# DXP_1602.net
KiCad netlist of a schematic drawn in Altium Designer
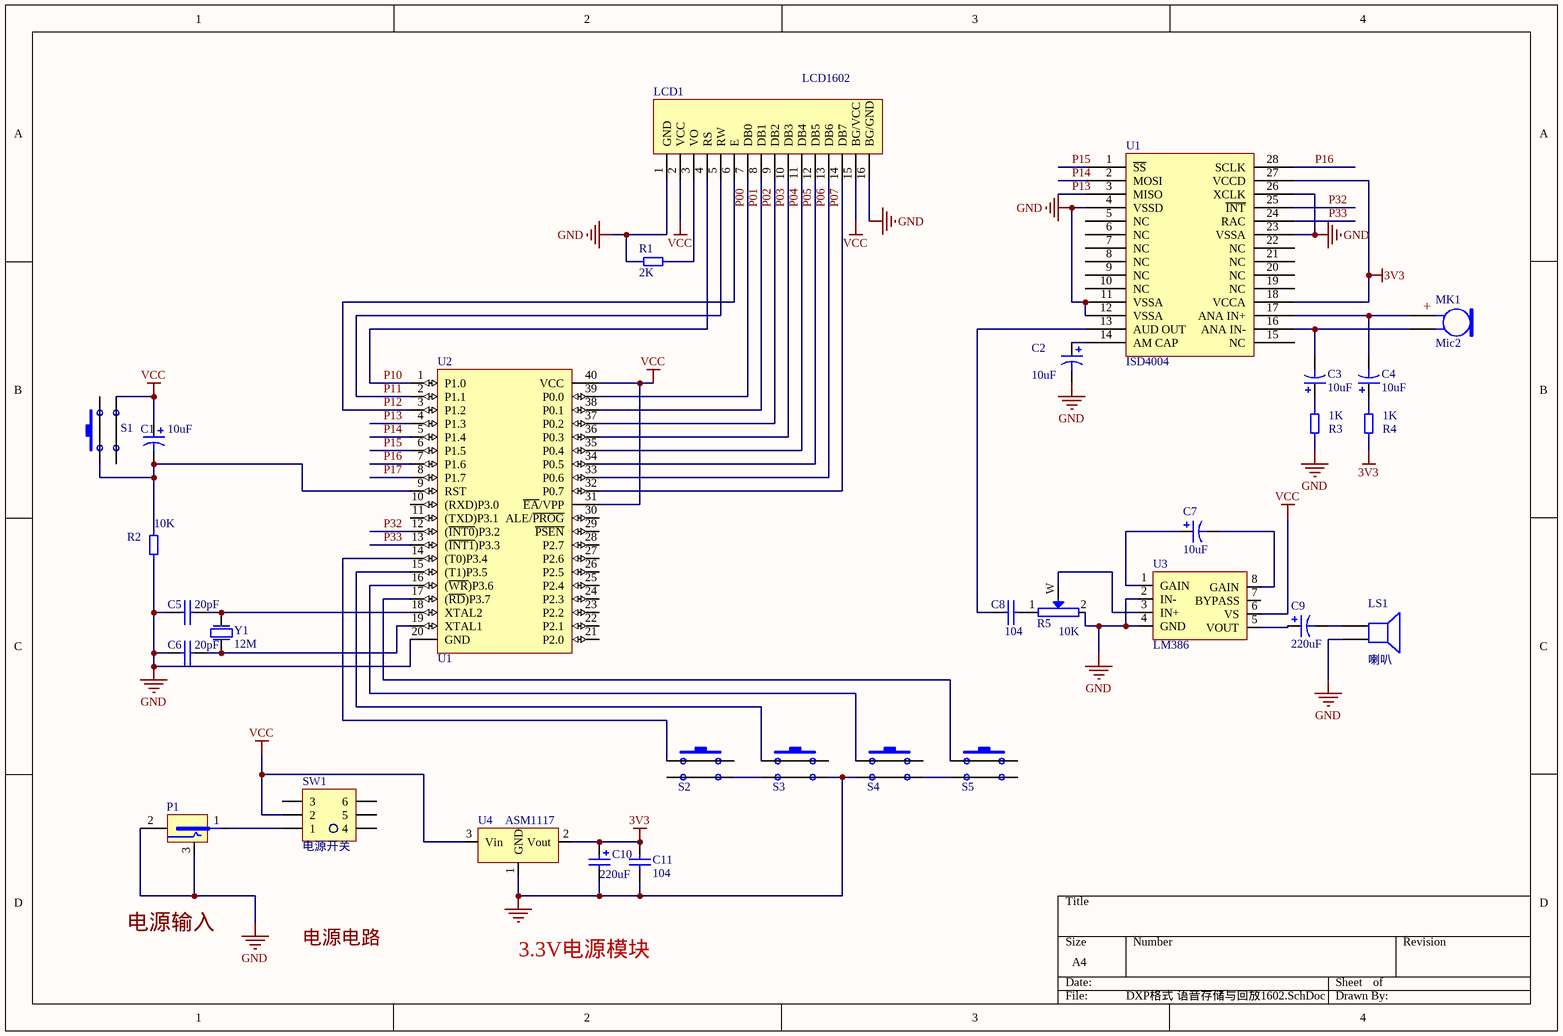
[diagram p0: DXP格式 语音存储与回放1602.SchDoc]

(export (version "E")
  (design (tool "Eeschema 10.0.6"))
  (components
    (comp (ref "C1")
      (value "10uF")
      (footprint "C_10")
      (description "Polarized Capacitor (Radial)")
      (fields (field (name "PUBLISHER") "Altium Limited"))
      (libsource (lib "简易动环监控系统") (part "Cap Pol1"))
    )
    (comp (ref "C2")
      (value "10uF")
      (footprint "C_10")
      (description "Polarized Capacitor (Radial)")
      (fields (field (name "PUBLISHER") "Altium Limited"))
      (libsource (lib "简易动环监控系统") (part "Cap Pol1"))
    )
    (comp (ref "C3")
      (value "10uF")
      (footprint "C_10")
      (description "Polarized Capacitor (Radial)")
      (fields (field (name "PUBLISHER") "Altium Limited"))
      (libsource (lib "简易动环监控系统") (part "Cap Pol1"))
    )
    (comp (ref "C4")
      (value "10uF")
      (footprint "C_10")
      (description "Polarized Capacitor (Radial)")
      (fields (field (name "PUBLISHER") "Altium Limited"))
      (libsource (lib "简易动环监控系统") (part "Cap Pol1"))
    )
    (comp (ref "C5")
      (value "20pF")
      (footprint "CAP CP")
      (description "电容")
      (libsource (lib "C8051F020最小2") (part "CAP"))
    )
    (comp (ref "C6")
      (value "20pF")
      (footprint "CAP CP")
      (description "电容")
      (libsource (lib "C8051F020最小2") (part "CAP"))
    )
    (comp (ref "C7")
      (value "10uF")
      (footprint "CAP_470")
      (description "Polarized Capacitor (Radial)")
      (fields (field (name "PUBLISHER") "Altium Limited"))
      (libsource (lib "简易动环监控系统") (part "Cap Pol1"))
    )
    (comp (ref "C8")
      (value "104")
      (footprint "CAP5")
      (description "电容")
      (libsource (lib "C8051F020最小2") (part "CAP"))
    )
    (comp (ref "C9")
      (value "220uF")
      (footprint "CAP_470")
      (description "Polarized Capacitor (Radial)")
      (fields (field (name "PUBLISHER") "Altium Limited"))
      (libsource (lib "简易动环监控系统") (part "Cap Pol1"))
    )
    (comp (ref "C10")
      (value "220uF")
      (footprint "C_10")
      (description "220uF 470uF 外径8mm 引脚3mm")
      (fields (field (name "Comment") "220uf"))
      (libsource (lib "*") (part "CAP 470uF"))
    )
    (comp (ref "C11")
      (value "104")
      (footprint "CAP CP")
      (description "瓷片电容")
      (libsource (lib "*") (part "CAP"))
    )
    (comp (ref "LCD1") (value "LCD1602") (footprint "1602") (libsource (lib "实用原理图库") (part "LCD1602")))
    (comp (ref "LS1")
      (value "喇叭")
      (footprint "SIP2")
      (description "Loudspeaker")
      (fields (field (name "PUBLISHER") "Altium Limited"))
      (libsource (lib "Miscellaneous Devices") (part "Speaker"))
    )
    (comp (ref "MK1")
      (value "Mic2")
      (footprint "mic")
      (description "Microphone")
      (fields (field (name "PUBLISHER") "Altium Limited"))
      (libsource (lib "Miscellaneous Devices") (part "Mic2"))
    )
    (comp (ref "P1") (value "电源输入") (footprint "DC2.1") (libsource (lib "我自己的") (part "POWER")))
    (comp (ref "R1") (value "2K") (footprint "AXIAL0.3") (libsource (lib "C8051F020最小2") (part "RES2")))
    (comp (ref "R2") (value "10K") (footprint "AXIAL0.3") (libsource (lib "C8051F020最小2") (part "RES2")))
    (comp (ref "R3") (value "1K") (footprint "AXIAL0.3") (libsource (lib "C8051F020最小2") (part "RES2")))
    (comp (ref "R4") (value "1K") (footprint "AXIAL0.3") (libsource (lib "C8051F020最小2") (part "RES2")))
    (comp (ref "R5")
      (value "10K")
      (footprint "RES")
      (description "可调电位器")
      (fields (field (name "Comment") "RES  KB"))
      (libsource (lib "JIANYANG") (part "RES  KB"))
    )
    (comp (ref "S1") (value "SW") (footprint "key") (libsource (lib "我自己的") (part "SW1_key")))
    (comp (ref "S2") (value "SW") (footprint "key") (libsource (lib "我自己的") (part "SW1_key")))
    (comp (ref "S3") (value "SW") (footprint "key") (libsource (lib "我自己的") (part "SW1_key")))
    (comp (ref "S4") (value "SW") (footprint "key") (libsource (lib "我自己的") (part "SW1_key")))
    (comp (ref "S5") (value "SW") (footprint "key") (libsource (lib "我自己的") (part "SW1_key")))
    (comp (ref "SW1") (value "电源开关") (footprint "sw_自锁 1") (libsource (lib "我自己的") (part "SW1")))
    (comp (ref "U1") (value "ISD4004") (footprint "DIP28") (libsource (lib "*") (part "ISD4004")))
    (comp (ref "U2") (value "U1") (footprint "DIP40 - 做板") (libsource (lib "实验板原理图") (part "U1")))
    (comp (ref "U3") (value "LM386") (footprint "DIP8") (libsource (lib "我自己的") (part "LM386")))
    (comp (ref "U4") (value "ASM1117") (footprint "ASM1117") (libsource (lib "*") (part "ASM1117")))
    (comp (ref "Y1")
      (value "12M")
      (footprint "XTAL")
      (description "Crystal Oscillator")
      (libsource (lib "C8051F020最小2") (part "16M"))
    )
  )
  (nets
    (net (code "2") (name "/P00") (class "Default")
      (node (ref "LCD1") (pin "7") (pinfunction "DB0_7") (pintype "passive"))
      (node (ref "U2") (pin "39") (pinfunction "P0.0_39") (pintype "bidirectional"))
    )
    (net (code "3") (name "/P01") (class "Default")
      (node (ref "LCD1") (pin "8") (pinfunction "DB1_8") (pintype "passive"))
      (node (ref "U2") (pin "38") (pinfunction "P0.1_38") (pintype "bidirectional"))
    )
    (net (code "4") (name "/P02") (class "Default")
      (node (ref "LCD1") (pin "9") (pinfunction "DB2_9") (pintype "passive"))
      (node (ref "U2") (pin "37") (pinfunction "P0.2_37") (pintype "bidirectional"))
    )
    (net (code "5") (name "/P03") (class "Default")
      (node (ref "LCD1") (pin "10") (pinfunction "DB3_10") (pintype "passive"))
      (node (ref "U2") (pin "36") (pinfunction "P0.3_36") (pintype "bidirectional"))
    )
    (net (code "6") (name "/P04") (class "Default")
      (node (ref "LCD1") (pin "11") (pinfunction "DB4_11") (pintype "passive"))
      (node (ref "U2") (pin "35") (pinfunction "P0.4_35") (pintype "bidirectional"))
    )
    (net (code "7") (name "/P05") (class "Default")
      (node (ref "LCD1") (pin "12") (pinfunction "DB5_12") (pintype "passive"))
      (node (ref "U2") (pin "34") (pinfunction "P0.5_34") (pintype "bidirectional"))
    )
    (net (code "8") (name "/P06") (class "Default")
      (node (ref "LCD1") (pin "13") (pinfunction "DB6_13") (pintype "passive"))
      (node (ref "U2") (pin "33") (pinfunction "P0.6_33") (pintype "bidirectional"))
    )
    (net (code "9") (name "/P07") (class "Default")
      (node (ref "LCD1") (pin "14") (pinfunction "DB7_14") (pintype "passive"))
      (node (ref "U2") (pin "32") (pinfunction "P0.7_32") (pintype "bidirectional"))
    )
    (net (code "10") (name "/P10") (class "Default")
      (node (ref "LCD1") (pin "4") (pinfunction "RS_4") (pintype "passive"))
      (node (ref "U2") (pin "1") (pinfunction "P1.0_1") (pintype "bidirectional"))
    )
    (net (code "11") (name "/P11") (class "Default")
      (node (ref "LCD1") (pin "5") (pinfunction "RW_5") (pintype "passive"))
      (node (ref "U2") (pin "2") (pinfunction "P1.1_2") (pintype "bidirectional"))
    )
    (net (code "12") (name "/P12") (class "Default")
      (node (ref "LCD1") (pin "6") (pinfunction "E_6") (pintype "passive"))
      (node (ref "U2") (pin "3") (pinfunction "P1.2_3") (pintype "bidirectional"))
    )
    (net (code "13") (name "/P13") (class "Default")
      (node (ref "U1") (pin "3") (pinfunction "MISO_3") (pintype "passive"))
      (node (ref "U2") (pin "4") (pinfunction "P1.3_4") (pintype "bidirectional"))
    )
    (net (code "14") (name "/P14") (class "Default")
      (node (ref "U1") (pin "2") (pinfunction "MOSI_2") (pintype "passive"))
      (node (ref "U2") (pin "5") (pinfunction "P1.4_5") (pintype "bidirectional"))
    )
    (net (code "15") (name "/P15") (class "Default")
      (node (ref "U1") (pin "1") (pinfunction "~{SS}_1") (pintype "passive"))
      (node (ref "U2") (pin "6") (pinfunction "P1.5_6") (pintype "bidirectional"))
    )
    (net (code "16") (name "/P16") (class "Default")
      (node (ref "U1") (pin "28") (pinfunction "SCLK_28") (pintype "passive"))
      (node (ref "U2") (pin "7") (pinfunction "P1.6_7") (pintype "bidirectional"))
    )
    (net (code "17") (name "/P17") (class "Default")
      (node (ref "U2") (pin "8") (pinfunction "P1.7_8") (pintype "bidirectional"))
    )
    (net (code "18") (name "/P32") (class "Default")
      (node (ref "U1") (pin "25") (pinfunction "~{INT}_25") (pintype "passive"))
      (node (ref "U2") (pin "12") (pinfunction "(~{INT0})P3.2_12") (pintype "bidirectional"))
    )
    (net (code "19") (name "/P33") (class "Default")
      (node (ref "U1") (pin "24") (pinfunction "RAC_24") (pintype "passive"))
      (node (ref "U2") (pin "13") (pinfunction "(~{INT1})P3.3_13") (pintype "bidirectional"))
    )
    (net (code "22") (name "3V3") (class "Default")
      (node (ref "C10") (pin "1") (pinfunction "1_1") (pintype "passive"))
      (node (ref "C11") (pin "2") (pinfunction "2_2") (pintype "passive"))
      (node (ref "R4") (pin "1") (pinfunction "1_1") (pintype "passive"))
      (node (ref "U1") (pin "18") (pinfunction "VCCA_18") (pintype "passive"))
      (node (ref "U1") (pin "27") (pinfunction "VCCD_27") (pintype "passive"))
      (node (ref "U4") (pin "2") (pinfunction "Vout_2") (pintype "passive"))
    )
    (net (code "23") (name "GND") (class "Default")
      (node (ref "C10") (pin "2") (pinfunction "2_2") (pintype "passive"))
      (node (ref "C11") (pin "1") (pinfunction "1_1") (pintype "passive"))
      (node (ref "C2") (pin "2") (pinfunction "2_2") (pintype "passive"))
      (node (ref "C5") (pin "1") (pinfunction "1_1") (pintype "passive"))
      (node (ref "C6") (pin "1") (pinfunction "1_1") (pintype "passive"))
      (node (ref "LCD1") (pin "1") (pinfunction "GND_1") (pintype "passive"))
      (node (ref "LCD1") (pin "16") (pinfunction "BG/GND_16") (pintype "passive"))
      (node (ref "LS1") (pin "2") (pinfunction "2_2") (pintype "passive"))
      (node (ref "P1") (pin "2") (pintype "passive"))
      (node (ref "P1") (pin "3") (pintype "passive"))
      (node (ref "R1") (pin "1") (pinfunction "1_1") (pintype "passive"))
      (node (ref "R2") (pin "1") (pinfunction "1_1") (pintype "passive"))
      (node (ref "R3") (pin "1") (pinfunction "1_1") (pintype "passive"))
      (node (ref "R5") (pin "2") (pintype "passive"))
      (node (ref "S3") (pin "2") (pinfunction "2_2") (pintype "passive"))
      (node (ref "S4") (pin "2") (pinfunction "2_2") (pintype "passive"))
      (node (ref "U1") (pin "11") (pinfunction "VSSA_11") (pintype "passive"))
      (node (ref "U1") (pin "12") (pinfunction "VSSA_12") (pintype "passive"))
      (node (ref "U1") (pin "23") (pinfunction "VSSA_23") (pintype "passive"))
      (node (ref "U1") (pin "26") (pinfunction "XCLK_26") (pintype "passive"))
      (node (ref "U1") (pin "4") (pinfunction "VSSD_4") (pintype "passive"))
      (node (ref "U2") (pin "20") (pinfunction "GND_20") (pintype "power_in"))
      (node (ref "U3") (pin "2") (pinfunction "IN-_2") (pintype "passive"))
      (node (ref "U3") (pin "4") (pinfunction "GND_4") (pintype "passive"))
      (node (ref "U4") (pin "1") (pinfunction "GND_1") (pintype "passive"))
    )
    (net (code "24") (name "Net-(C3-Pad1)") (class "Default")
      (node (ref "C3") (pin "1") (pinfunction "1_1") (pintype "passive"))
      (node (ref "R3") (pin "2") (pinfunction "2_2") (pintype "passive"))
    )
    (net (code "25") (name "Net-(C4-Pad1)") (class "Default")
      (node (ref "C4") (pin "1") (pinfunction "1_1") (pintype "passive"))
      (node (ref "R4") (pin "2") (pinfunction "2_2") (pintype "passive"))
    )
    (net (code "26") (name "Net-(C7-Pad1)") (class "Default")
      (node (ref "C7") (pin "1") (pinfunction "1_1") (pintype "passive"))
      (node (ref "U3") (pin "1") (pinfunction "GAIN_1") (pintype "passive"))
    )
    (net (code "27") (name "Net-(C7-Pad2)") (class "Default")
      (node (ref "C7") (pin "2") (pinfunction "2_2") (pintype "passive"))
      (node (ref "U3") (pin "8") (pinfunction "GAIN_8") (pintype "passive"))
    )
    (net (code "28") (name "Net-(C8-Pad2)") (class "Default")
      (node (ref "C8") (pin "2") (pinfunction "2_2") (pintype "passive"))
      (node (ref "R5") (pin "1") (pintype "passive"))
    )
    (net (code "29") (name "Net-(C9-Pad2)") (class "Default")
      (node (ref "C9") (pin "2") (pinfunction "2_2") (pintype "passive"))
      (node (ref "LS1") (pin "1") (pinfunction "1_1") (pintype "passive"))
    )
    (net (code "30") (name "Net-(LCD1-VO)") (class "Default")
      (node (ref "LCD1") (pin "3") (pinfunction "VO_3") (pintype "passive"))
      (node (ref "R1") (pin "2") (pinfunction "2_2") (pintype "passive"))
    )
    (net (code "31") (name "Net-(P1-Pad1)") (class "Default")
      (node (ref "P1") (pin "1") (pintype "passive"))
      (node (ref "SW1") (pin "1") (pinfunction "1_1") (pintype "passive"))
    )
    (net (code "32") (name "Net-(S2-Pad2)_1") (class "Default")
      (node (ref "S2") (pin "2") (pinfunction "2_2") (pintype "passive"))
      (node (ref "S3") (pin "2") (pinfunction "2_2") (pintype "passive"))
    )
    (net (code "33") (name "Net-(S4-Pad2)") (class "Default")
      (node (ref "S4") (pin "2") (pinfunction "2_2") (pintype "passive"))
      (node (ref "S5") (pin "2") (pinfunction "2_2") (pintype "passive"))
    )
    (net (code "34") (name "Net-(U1-AM_CAP)") (class "Default")
      (node (ref "C2") (pin "1") (pinfunction "1_1") (pintype "passive"))
      (node (ref "U1") (pin "14") (pinfunction "AM_CAP_14") (pintype "passive"))
    )
    (net (code "35") (name "Net-(U1-ANA_IN+)") (class "Default")
      (node (ref "C4") (pin "2") (pinfunction "2_2") (pintype "passive"))
      (node (ref "MK1") (pin "1") (pinfunction "1_1") (pintype "passive"))
      (node (ref "U1") (pin "17") (pinfunction "ANA_IN+_17") (pintype "passive"))
    )
    (net (code "36") (name "Net-(U1-ANA_IN-)") (class "Default")
      (node (ref "C3") (pin "2") (pinfunction "2_2") (pintype "passive"))
      (node (ref "MK1") (pin "2") (pinfunction "2_2") (pintype "passive"))
      (node (ref "U1") (pin "16") (pinfunction "ANA_IN-_16") (pintype "passive"))
    )
    (net (code "37") (name "Net-(U1-AUD_OUT)") (class "Default")
      (node (ref "C8") (pin "1") (pinfunction "1_1") (pintype "passive"))
      (node (ref "U1") (pin "13") (pinfunction "AUD_OUT_13") (pintype "passive"))
    )
    (net (code "38") (name "Net-(U2-(T0)P3.4)") (class "Default")
      (node (ref "S2") (pin "1") (pinfunction "1_1") (pintype "passive"))
      (node (ref "U2") (pin "14") (pinfunction "(T0)P3.4_14") (pintype "bidirectional"))
    )
    (net (code "39") (name "Net-(U2-(T1)P3.5)") (class "Default")
      (node (ref "S3") (pin "1") (pinfunction "1_1") (pintype "passive"))
      (node (ref "U2") (pin "15") (pinfunction "(T1)P3.5_15") (pintype "bidirectional"))
    )
    (net (code "40") (name "Net-(U2-(~{RD})P3.7)") (class "Default")
      (node (ref "S5") (pin "1") (pinfunction "1_1") (pintype "passive"))
      (node (ref "U2") (pin "17") (pinfunction "(~{RD})P3.7_17") (pintype "bidirectional"))
    )
    (net (code "41") (name "Net-(U2-(~{WR})P3.6)") (class "Default")
      (node (ref "S4") (pin "1") (pinfunction "1_1") (pintype "passive"))
      (node (ref "U2") (pin "16") (pinfunction "(~{WR})P3.6_16") (pintype "bidirectional"))
    )
    (net (code "42") (name "Net-(U2-RST)") (class "Default")
      (node (ref "C1") (pin "2") (pinfunction "2_2") (pintype "passive"))
      (node (ref "R2") (pin "2") (pinfunction "2_2") (pintype "passive"))
      (node (ref "S1") (pin "1") (pinfunction "1_1") (pintype "passive"))
      (node (ref "U2") (pin "9") (pinfunction "RST_9") (pintype "bidirectional"))
    )
    (net (code "43") (name "Net-(U2-XTAL1)") (class "Default")
      (node (ref "C6") (pin "2") (pinfunction "2_2") (pintype "passive"))
      (node (ref "U2") (pin "19") (pinfunction "XTAL1_19") (pintype "bidirectional"))
      (node (ref "Y1") (pin "2") (pinfunction "P2_2") (pintype "passive"))
    )
    (net (code "44") (name "Net-(U2-XTAL2)") (class "Default")
      (node (ref "C5") (pin "2") (pinfunction "2_2") (pintype "passive"))
      (node (ref "U2") (pin "18") (pinfunction "XTAL2_18") (pintype "bidirectional"))
      (node (ref "Y1") (pin "1") (pinfunction "P1_1") (pintype "passive"))
    )
    (net (code "45") (name "Net-(U3-IN+)") (class "Default")
      (node (ref "R5") (pin "W") (pintype "passive"))
      (node (ref "U3") (pin "3") (pinfunction "IN+_3") (pintype "passive"))
    )
    (net (code "46") (name "Net-(U3-VOUT)") (class "Default")
      (node (ref "C9") (pin "1") (pinfunction "1_1") (pintype "passive"))
      (node (ref "U3") (pin "5") (pinfunction "VOUT_5") (pintype "passive"))
    )
    (net (code "47") (name "VCC") (class "Default")
      (node (ref "C1") (pin "1") (pinfunction "1_1") (pintype "passive"))
      (node (ref "LCD1") (pin "15") (pinfunction "BG/VCC_15") (pintype "passive"))
      (node (ref "LCD1") (pin "2") (pinfunction "VCC_2") (pintype "passive"))
      (node (ref "S1") (pin "2") (pinfunction "2_2") (pintype "passive"))
      (node (ref "SW1") (pin "2") (pinfunction "2_2") (pintype "passive"))
      (node (ref "U2") (pin "31") (pinfunction "~{EA}/VPP_31") (pintype "power_in"))
      (node (ref "U2") (pin "40") (pinfunction "VCC_40") (pintype "power_in"))
      (node (ref "U3") (pin "6") (pinfunction "VS_6") (pintype "passive"))
      (node (ref "U4") (pin "3") (pinfunction "Vin_3") (pintype "passive"))
    )
    (net (code "48") (name "unconnected-(S1-Pad1)") (class "Default")
      (node (ref "S1") (pin "1") (pinfunction "1_1") (pintype "passive"))
    )
    (net (code "49") (name "unconnected-(S1-Pad2)") (class "Default")
      (node (ref "S1") (pin "2") (pinfunction "2_2") (pintype "passive"))
    )
    (net (code "50") (name "unconnected-(S2-Pad1)") (class "Default")
      (node (ref "S2") (pin "1") (pinfunction "1_1") (pintype "passive"))
    )
    (net (code "51") (name "unconnected-(S2-Pad2)") (class "Default")
      (node (ref "S2") (pin "2") (pinfunction "2_2") (pintype "passive"))
    )
    (net (code "52") (name "unconnected-(S3-Pad1)") (class "Default")
      (node (ref "S3") (pin "1") (pinfunction "1_1") (pintype "passive"))
    )
    (net (code "53") (name "unconnected-(S4-Pad1)") (class "Default")
      (node (ref "S4") (pin "1") (pinfunction "1_1") (pintype "passive"))
    )
    (net (code "54") (name "unconnected-(S5-Pad1)") (class "Default")
      (node (ref "S5") (pin "1") (pinfunction "1_1") (pintype "passive"))
    )
    (net (code "55") (name "unconnected-(S5-Pad2)") (class "Default")
      (node (ref "S5") (pin "2") (pinfunction "2_2") (pintype "passive"))
    )
    (net (code "56") (name "unconnected-(SW1-Pad3)") (class "Default")
      (node (ref "SW1") (pin "3") (pinfunction "3_3") (pintype "passive"))
    )
    (net (code "57") (name "unconnected-(SW1-Pad4)") (class "Default")
      (node (ref "SW1") (pin "4") (pinfunction "4_4") (pintype "passive"))
    )
    (net (code "58") (name "unconnected-(SW1-Pad5)") (class "Default")
      (node (ref "SW1") (pin "5") (pinfunction "5_5") (pintype "passive"))
    )
    (net (code "59") (name "unconnected-(SW1-Pad6)") (class "Default")
      (node (ref "SW1") (pin "6") (pinfunction "6_6") (pintype "passive"))
    )
    (net (code "60") (name "unconnected-(U1-NC-Pad5)") (class "Default")
      (node (ref "U1") (pin "5") (pinfunction "NC_5") (pintype "passive"))
    )
    (net (code "61") (name "unconnected-(U1-NC-Pad6)") (class "Default")
      (node (ref "U1") (pin "6") (pinfunction "NC_6") (pintype "passive"))
    )
    (net (code "62") (name "unconnected-(U1-NC-Pad7)") (class "Default")
      (node (ref "U1") (pin "7") (pinfunction "NC_7") (pintype "passive"))
    )
    (net (code "63") (name "unconnected-(U1-NC-Pad8)") (class "Default")
      (node (ref "U1") (pin "8") (pinfunction "NC_8") (pintype "passive"))
    )
    (net (code "64") (name "unconnected-(U1-NC-Pad9)") (class "Default")
      (node (ref "U1") (pin "9") (pinfunction "NC_9") (pintype "passive"))
    )
    (net (code "65") (name "unconnected-(U1-NC-Pad10)") (class "Default")
      (node (ref "U1") (pin "10") (pinfunction "NC_10") (pintype "passive"))
    )
    (net (code "66") (name "unconnected-(U1-NC-Pad15)") (class "Default")
      (node (ref "U1") (pin "15") (pinfunction "NC_15") (pintype "passive"))
    )
    (net (code "67") (name "unconnected-(U1-NC-Pad19)") (class "Default")
      (node (ref "U1") (pin "19") (pinfunction "NC_19") (pintype "passive"))
    )
    (net (code "68") (name "unconnected-(U1-NC-Pad20)") (class "Default")
      (node (ref "U1") (pin "20") (pinfunction "NC_20") (pintype "passive"))
    )
    (net (code "69") (name "unconnected-(U1-NC-Pad21)") (class "Default")
      (node (ref "U1") (pin "21") (pinfunction "NC_21") (pintype "passive"))
    )
    (net (code "70") (name "unconnected-(U1-NC-Pad22)") (class "Default")
      (node (ref "U1") (pin "22") (pinfunction "NC_22") (pintype "passive"))
    )
    (net (code "71") (name "unconnected-(U2-(RXD)P3.0-Pad10)") (class "Default")
      (node (ref "U2") (pin "10") (pinfunction "(RXD)P3.0_10") (pintype "bidirectional"))
    )
    (net (code "72") (name "unconnected-(U2-(TXD)P3.1-Pad11)") (class "Default")
      (node (ref "U2") (pin "11") (pinfunction "(TXD)P3.1_11") (pintype "bidirectional"))
    )
    (net (code "73") (name "unconnected-(U2-ALE{slash}~{PROG}-Pad30)") (class "Default")
      (node (ref "U2") (pin "30") (pinfunction "ALE/~{PROG}_30") (pintype "bidirectional"))
    )
    (net (code "74") (name "unconnected-(U2-P2.0-Pad21)") (class "Default")
      (node (ref "U2") (pin "21") (pinfunction "P2.0_21") (pintype "bidirectional"))
    )
    (net (code "75") (name "unconnected-(U2-P2.1-Pad22)") (class "Default")
      (node (ref "U2") (pin "22") (pinfunction "P2.1_22") (pintype "bidirectional"))
    )
    (net (code "76") (name "unconnected-(U2-P2.2-Pad23)") (class "Default")
      (node (ref "U2") (pin "23") (pinfunction "P2.2_23") (pintype "bidirectional"))
    )
    (net (code "77") (name "unconnected-(U2-P2.3-Pad24)") (class "Default")
      (node (ref "U2") (pin "24") (pinfunction "P2.3_24") (pintype "bidirectional"))
    )
    (net (code "78") (name "unconnected-(U2-P2.4-Pad25)") (class "Default")
      (node (ref "U2") (pin "25") (pinfunction "P2.4_25") (pintype "bidirectional"))
    )
    (net (code "79") (name "unconnected-(U2-P2.5-Pad26)") (class "Default")
      (node (ref "U2") (pin "26") (pinfunction "P2.5_26") (pintype "bidirectional"))
    )
    (net (code "80") (name "unconnected-(U2-P2.6-Pad27)") (class "Default")
      (node (ref "U2") (pin "27") (pinfunction "P2.6_27") (pintype "bidirectional"))
    )
    (net (code "81") (name "unconnected-(U2-P2.7-Pad28)") (class "Default")
      (node (ref "U2") (pin "28") (pinfunction "P2.7_28") (pintype "bidirectional"))
    )
    (net (code "82") (name "unconnected-(U2-~{PSEN}-Pad29)") (class "Default")
      (node (ref "U2") (pin "29") (pinfunction "~{PSEN}_29") (pintype "bidirectional"))
    )
    (net (code "83") (name "unconnected-(U3-BYPASS-Pad7)") (class "Default")
      (node (ref "U3") (pin "7") (pinfunction "BYPASS_7") (pintype "passive"))
    )
  )
)
